# 00-Main.net
KiCad netlist of a schematic drawn in Altium Designer
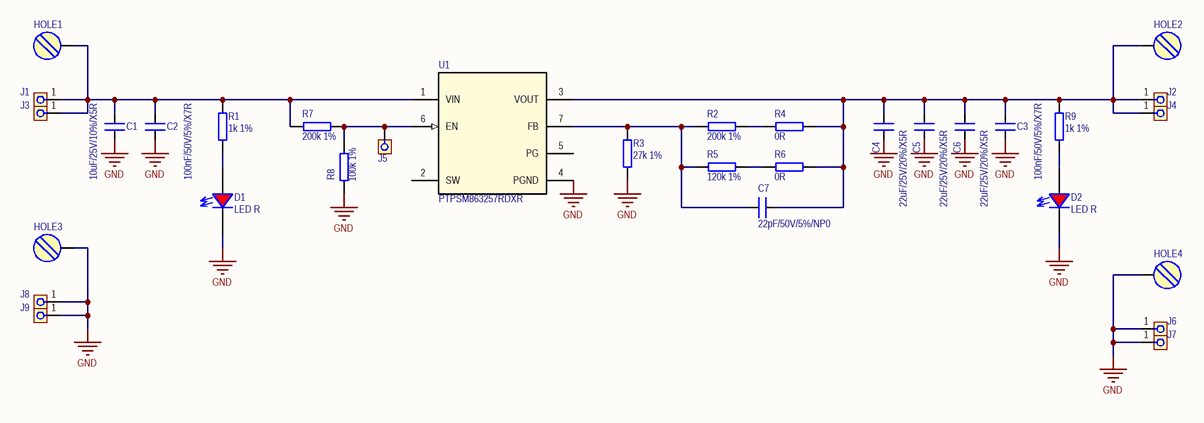
[diagram p0: 00-Main.SchDoc]

(export (version "E")
  (design (tool "Eeschema 10.0.6"))
  (components
    (comp (ref "C1")
      (value "10uF/25V/10%/X5R")
      (footprint "C-0805")
      (description "SMD Ceramic Capacitor 0805 10uF/25V/10%/X5R")
      (fields (field (name "TOLERANCE") "10%") (field (name "VOLTAGE") "25V"))
      (libsource (lib "Y Soft Corporation, a.s") (part "CapacitorNP"))
    )
    (comp (ref "C2")
      (value "100nF/50V/5%/X7R")
      (footprint "C-0603")
      (description "SMD Ceramic Capacitor 0603 100nF/50V/5%/X7R")
      (fields (field (name "TOLERANCE") "5%") (field (name "VOLTAGE") "50V"))
      (libsource (lib "Y Soft Corporation, a.s") (part "CapacitorNP"))
    )
    (comp (ref "C3")
      (value "100nF/50V/5%/X7R")
      (footprint "C-0603")
      (description "SMD Ceramic Capacitor 0603 100nF/50V/5%/X7R")
      (fields (field (name "TOLERANCE") "5%") (field (name "VOLTAGE") "50V"))
      (libsource (lib "Y Soft Corporation, a.s") (part "CapacitorNP"))
    )
    (comp (ref "C4")
      (value "22uF/25V/20%/X5R")
      (footprint "C-0805")
      (description "SMD Ceramic Capacitor 0805 22uF/25V/20%/X5R")
      (fields (field (name "VOLTAGE") "25V") (field (name "TOLERANCE") "20%"))
      (libsource (lib "Y Soft Corporation, a.s") (part "CapacitorNP"))
    )
    (comp (ref "C5")
      (value "22uF/25V/20%/X5R")
      (footprint "C-0805")
      (description "SMD Ceramic Capacitor 0805 22uF/25V/20%/X5R")
      (fields (field (name "VOLTAGE") "25V") (field (name "TOLERANCE") "20%"))
      (libsource (lib "Y Soft Corporation, a.s") (part "CapacitorNP"))
    )
    (comp (ref "C6")
      (value "22uF/25V/20%/X5R")
      (footprint "C-0805")
      (description "SMD Ceramic Capacitor 0805 22uF/25V/20%/X5R")
      (fields (field (name "VOLTAGE") "25V") (field (name "TOLERANCE") "20%"))
      (libsource (lib "Y Soft Corporation, a.s") (part "CapacitorNP"))
    )
    (comp (ref "C7")
      (value "22pF/50V/5%/NP0")
      (footprint "C-0603")
      (description "SMD Ceramic Capacitor 0603 22pF/50V/5%/NP0")
      (fields (field (name "VOLTAGE") "50V") (field (name "TOLERANCE") "5%"))
      (libsource (lib "Y Soft Corporation, a.s") (part "CapacitorNP"))
    )
    (comp (ref "D1")
      (value "LED R")
      (footprint "LED-0603 RED")
      (description "LED; SMD; 0603; červená; 8-15mcd; 1,6x0,8x1,1mm; 150°; 2,0÷2,5V; 20mA")
      (libsource (lib "Y Soft Corporation, a.s") (part "LED-R"))
    )
    (comp (ref "D2")
      (value "LED R")
      (footprint "LED-0603 RED")
      (description "LED; SMD; 0603; červená; 8-15mcd; 1,6x0,8x1,1mm; 150°; 2,0÷2,5V; 20mA")
      (libsource (lib "Y Soft Corporation, a.s") (part "LED-R"))
    )
    (comp (ref "HOLE1")
      (value "Hole M2.5 screw")
      (footprint "M2.5 Screw hole")
      (description "Hole for M2.5 screw")
      (libsource (lib "Y Soft Corporation, a.s") (part "Hole Connected"))
    )
    (comp (ref "HOLE2")
      (value "Hole M2.5 screw")
      (footprint "M2.5 Screw hole")
      (description "Hole for M2.5 screw")
      (libsource (lib "Y Soft Corporation, a.s") (part "Hole Connected"))
    )
    (comp (ref "HOLE3")
      (value "Hole M2.5 screw")
      (footprint "M2.5 Screw hole")
      (description "Hole for M2.5 screw")
      (libsource (lib "Y Soft Corporation, a.s") (part "Hole Connected"))
    )
    (comp (ref "HOLE4")
      (value "Hole M2.5 screw")
      (footprint "M2.5 Screw hole")
      (description "Hole for M2.5 screw")
      (libsource (lib "Y Soft Corporation, a.s") (part "Hole Connected"))
    )
    (comp (ref "J1")
      (value "PAD1G01")
      (footprint "HDR1X01S")
      (description "1x1pin single pad")
      (libsource (lib "") (part "Pin 01_2"))
    )
    (comp (ref "J2")
      (value "PAD1G01")
      (footprint "HDR1X01S")
      (description "1x1pin single pad")
      (libsource (lib "Y Soft Corporation, a.s") (part "Pin 01"))
    )
    (comp (ref "J3")
      (value "PAD1G01")
      (footprint "HDR1X01S")
      (description "1x1pin single pad")
      (libsource (lib "") (part "Pin 01_2"))
    )
    (comp (ref "J4")
      (value "PAD1G01")
      (footprint "HDR1X01S")
      (description "1x1pin single pad")
      (libsource (lib "Y Soft Corporation, a.s") (part "Pin 01"))
    )
    (comp (ref "J5")
      (value "PAD1G01")
      (footprint "HDR1X01S")
      (description "1x1pin single pad")
      (libsource (lib "") (part "Pin 01_1"))
    )
    (comp (ref "J6")
      (value "PAD1G01")
      (footprint "HDR1X01S")
      (description "1x1pin single pad")
      (libsource (lib "Y Soft Corporation, a.s") (part "Pin 01"))
    )
    (comp (ref "J7")
      (value "PAD1G01")
      (footprint "HDR1X01S")
      (description "1x1pin single pad")
      (libsource (lib "Y Soft Corporation, a.s") (part "Pin 01"))
    )
    (comp (ref "J8")
      (value "PAD1G01")
      (footprint "HDR1X01S")
      (description "1x1pin single pad")
      (libsource (lib "") (part "Pin 01_2"))
    )
    (comp (ref "J9")
      (value "PAD1G01")
      (footprint "HDR1X01S")
      (description "1x1pin single pad")
      (libsource (lib "") (part "Pin 01_2"))
    )
    (comp (ref "R1")
      (value "1k 1%")
      (footprint "R-0603")
      (description "SMD Resistor 0603 1k 1%")
      (fields (field (name "POWER") "100mW") (field (name "TOLERANCE") "1%"))
      (libsource (lib "Y Soft Corporation, a.s") (part "Resistor"))
    )
    (comp (ref "R2")
      (value "200k 1%")
      (footprint "R-0603")
      (description "SMD Resistor 0603 200k 1%")
      (fields (field (name "POWER") "100mW") (field (name "TOLERANCE") "5%"))
      (libsource (lib "Y Soft Corporation, a.s") (part "Resistor"))
    )
    (comp (ref "R3")
      (value "27k 1%")
      (footprint "R-0603")
      (description "SMD Resistor 0603 27k 1%")
      (fields (field (name "POWER") "100mW") (field (name "TOLERANCE") "1%"))
      (libsource (lib "Y Soft Corporation, a.s") (part "Resistor"))
    )
    (comp (ref "R4")
      (value "0R")
      (footprint "R-0603-SB")
      (description "SMD Resistor 0603 0R")
      (fields (field (name "POWER") "100mW") (field (name "TOLERANCE") "5%"))
      (libsource (lib "Y Soft Corporation, a.s") (part "Resistor"))
    )
    (comp (ref "R5")
      (value "120k 1%")
      (footprint "R-0603")
      (description "SMD Resistor 0603 120k 1%")
      (fields (field (name "POWER") "100mW") (field (name "TOLERANCE") "1%"))
      (libsource (lib "Y Soft Corporation, a.s") (part "Resistor"))
    )
    (comp (ref "R6")
      (value "0R")
      (footprint "R-0603-SB")
      (description "SMD Resistor 0603 0R")
      (fields (field (name "POWER") "100mW") (field (name "TOLERANCE") "5%"))
      (libsource (lib "Y Soft Corporation, a.s") (part "Resistor"))
    )
    (comp (ref "R7")
      (value "200k 1%")
      (footprint "R-0603")
      (description "SMD Resistor 0603 200k 1%")
      (fields (field (name "POWER") "100mW") (field (name "TOLERANCE") "5%"))
      (libsource (lib "Y Soft Corporation, a.s") (part "Resistor"))
    )
    (comp (ref "R8")
      (value "100k 1%")
      (footprint "R-0603")
      (description "SMD Resistor 0603 100k 1%")
      (fields (field (name "POWER") "100mW") (field (name "TOLERANCE") "1%"))
      (libsource (lib "Y Soft Corporation, a.s") (part "Resistor"))
    )
    (comp (ref "R9")
      (value "1k 1%")
      (footprint "R-0603")
      (description "SMD Resistor 0603 1k 1%")
      (fields (field (name "POWER") "100mW") (field (name "TOLERANCE") "1%"))
      (libsource (lib "Y Soft Corporation, a.s") (part "Resistor"))
    )
    (comp (ref "U1")
      (value "PTPSM863257RDXR")
      (footprint "RDX0007A-MFG")
      (description "3-V to 17-V input voltage, 3-A forced-CCM synchronous buck module 7-QFN-FCMOD -40 to 125")
      (fields (field (name "COPYRIGHT") "Copyright (C) 2026 Ultra Librarian. All rights reserved."))
      (libsource (lib "PTPSM863257RDXR") (part "PTPSM863257RDXR"))
    )
  )
  (nets
    (net (code "1") (name "GND") (class "Default")
      (node (ref "C1") (pin "1") (pinfunction "1_1") (pintype "passive"))
      (node (ref "C2") (pin "1") (pinfunction "1_1") (pintype "passive"))
      (node (ref "C3") (pin "1") (pinfunction "1_1") (pintype "passive"))
      (node (ref "C4") (pin "1") (pinfunction "1_1") (pintype "passive"))
      (node (ref "C5") (pin "1") (pinfunction "1_1") (pintype "passive"))
      (node (ref "C6") (pin "1") (pinfunction "1_1") (pintype "passive"))
      (node (ref "D1") (pin "1") (pinfunction "K_1") (pintype "passive"))
      (node (ref "D2") (pin "1") (pinfunction "K_1") (pintype "passive"))
      (node (ref "HOLE3") (pin "1") (pinfunction "1_1") (pintype "passive"))
      (node (ref "HOLE4") (pin "1") (pinfunction "1_1") (pintype "passive"))
      (node (ref "J6") (pin "1") (pinfunction "1_1") (pintype "passive"))
      (node (ref "J7") (pin "1") (pinfunction "1_1") (pintype "passive"))
      (node (ref "J8") (pin "1") (pinfunction "1_1") (pintype "passive"))
      (node (ref "J9") (pin "1") (pinfunction "1_1") (pintype "passive"))
      (node (ref "R3") (pin "2") (pinfunction "2_2") (pintype "passive"))
      (node (ref "R8") (pin "1") (pinfunction "1_1") (pintype "passive"))
      (node (ref "U1") (pin "4") (pinfunction "PGND_4") (pintype "power_in"))
    )
    (net (code "2") (name "Net-(D1-A)") (class "Default")
      (node (ref "D1") (pin "2") (pinfunction "A_2") (pintype "passive"))
      (node (ref "R1") (pin "2") (pinfunction "2_2") (pintype "passive"))
    )
    (net (code "3") (name "Net-(D2-A)") (class "Default")
      (node (ref "D2") (pin "2") (pinfunction "A_2") (pintype "passive"))
      (node (ref "R9") (pin "2") (pinfunction "2_2") (pintype "passive"))
    )
    (net (code "4") (name "Net-(R2-Pad2)") (class "Default")
      (node (ref "R2") (pin "2") (pinfunction "2_2") (pintype "passive"))
      (node (ref "R4") (pin "1") (pinfunction "1_1") (pintype "passive"))
    )
    (net (code "5") (name "Net-(R5-Pad2)") (class "Default")
      (node (ref "R5") (pin "2") (pinfunction "2_2") (pintype "passive"))
      (node (ref "R6") (pin "1") (pinfunction "1_1") (pintype "passive"))
    )
    (net (code "6") (name "Net-(U1-EN)") (class "Default")
      (node (ref "J5") (pin "1") (pinfunction "1_1") (pintype "passive"))
      (node (ref "R7") (pin "2") (pinfunction "2_2") (pintype "passive"))
      (node (ref "R8") (pin "2") (pinfunction "2_2") (pintype "passive"))
      (node (ref "U1") (pin "6") (pinfunction "EN_6") (pintype "input"))
    )
    (net (code "7") (name "Net-(U1-FB)") (class "Default")
      (node (ref "C7") (pin "1") (pinfunction "1_1") (pintype "passive"))
      (node (ref "R2") (pin "1") (pinfunction "1_1") (pintype "passive"))
      (node (ref "R3") (pin "1") (pinfunction "1_1") (pintype "passive"))
      (node (ref "R5") (pin "1") (pinfunction "1_1") (pintype "passive"))
      (node (ref "U1") (pin "7") (pinfunction "FB_7") (pintype "passive"))
    )
    (net (code "8") (name "Net-(U1-VIN)") (class "Default")
      (node (ref "C1") (pin "2") (pinfunction "2_2") (pintype "passive"))
      (node (ref "C2") (pin "2") (pinfunction "2_2") (pintype "passive"))
      (node (ref "HOLE1") (pin "1") (pinfunction "1_1") (pintype "passive"))
      (node (ref "J1") (pin "1") (pinfunction "1_1") (pintype "passive"))
      (node (ref "J3") (pin "1") (pinfunction "1_1") (pintype "passive"))
      (node (ref "R1") (pin "1") (pinfunction "1_1") (pintype "passive"))
      (node (ref "R7") (pin "1") (pinfunction "1_1") (pintype "passive"))
      (node (ref "U1") (pin "1") (pinfunction "VIN_1") (pintype "power_in"))
    )
    (net (code "9") (name "Net-(U1-VOUT)") (class "Default")
      (node (ref "C3") (pin "2") (pinfunction "2_2") (pintype "passive"))
      (node (ref "C4") (pin "2") (pinfunction "2_2") (pintype "passive"))
      (node (ref "C5") (pin "2") (pinfunction "2_2") (pintype "passive"))
      (node (ref "C6") (pin "2") (pinfunction "2_2") (pintype "passive"))
      (node (ref "C7") (pin "2") (pinfunction "2_2") (pintype "passive"))
      (node (ref "HOLE2") (pin "1") (pinfunction "1_1") (pintype "passive"))
      (node (ref "J2") (pin "1") (pinfunction "1_1") (pintype "passive"))
      (node (ref "J4") (pin "1") (pinfunction "1_1") (pintype "passive"))
      (node (ref "R4") (pin "2") (pinfunction "2_2") (pintype "passive"))
      (node (ref "R6") (pin "2") (pinfunction "2_2") (pintype "passive"))
      (node (ref "R9") (pin "1") (pinfunction "1_1") (pintype "passive"))
      (node (ref "U1") (pin "3") (pinfunction "VOUT_3") (pintype "power_in"))
    )
    (net (code "10") (name "unconnected-(U1-PG-Pad5)") (class "Default")
      (node (ref "U1") (pin "5") (pinfunction "PG_5") (pintype "open_collector"))
    )
    (net (code "11") (name "unconnected-(U1-SW-Pad2)") (class "Default")
      (node (ref "U1") (pin "2") (pinfunction "SW_2") (pintype "passive"))
    )
  )
)
